# U_I.net
KiCad netlist of a schematic drawn in EAGLE
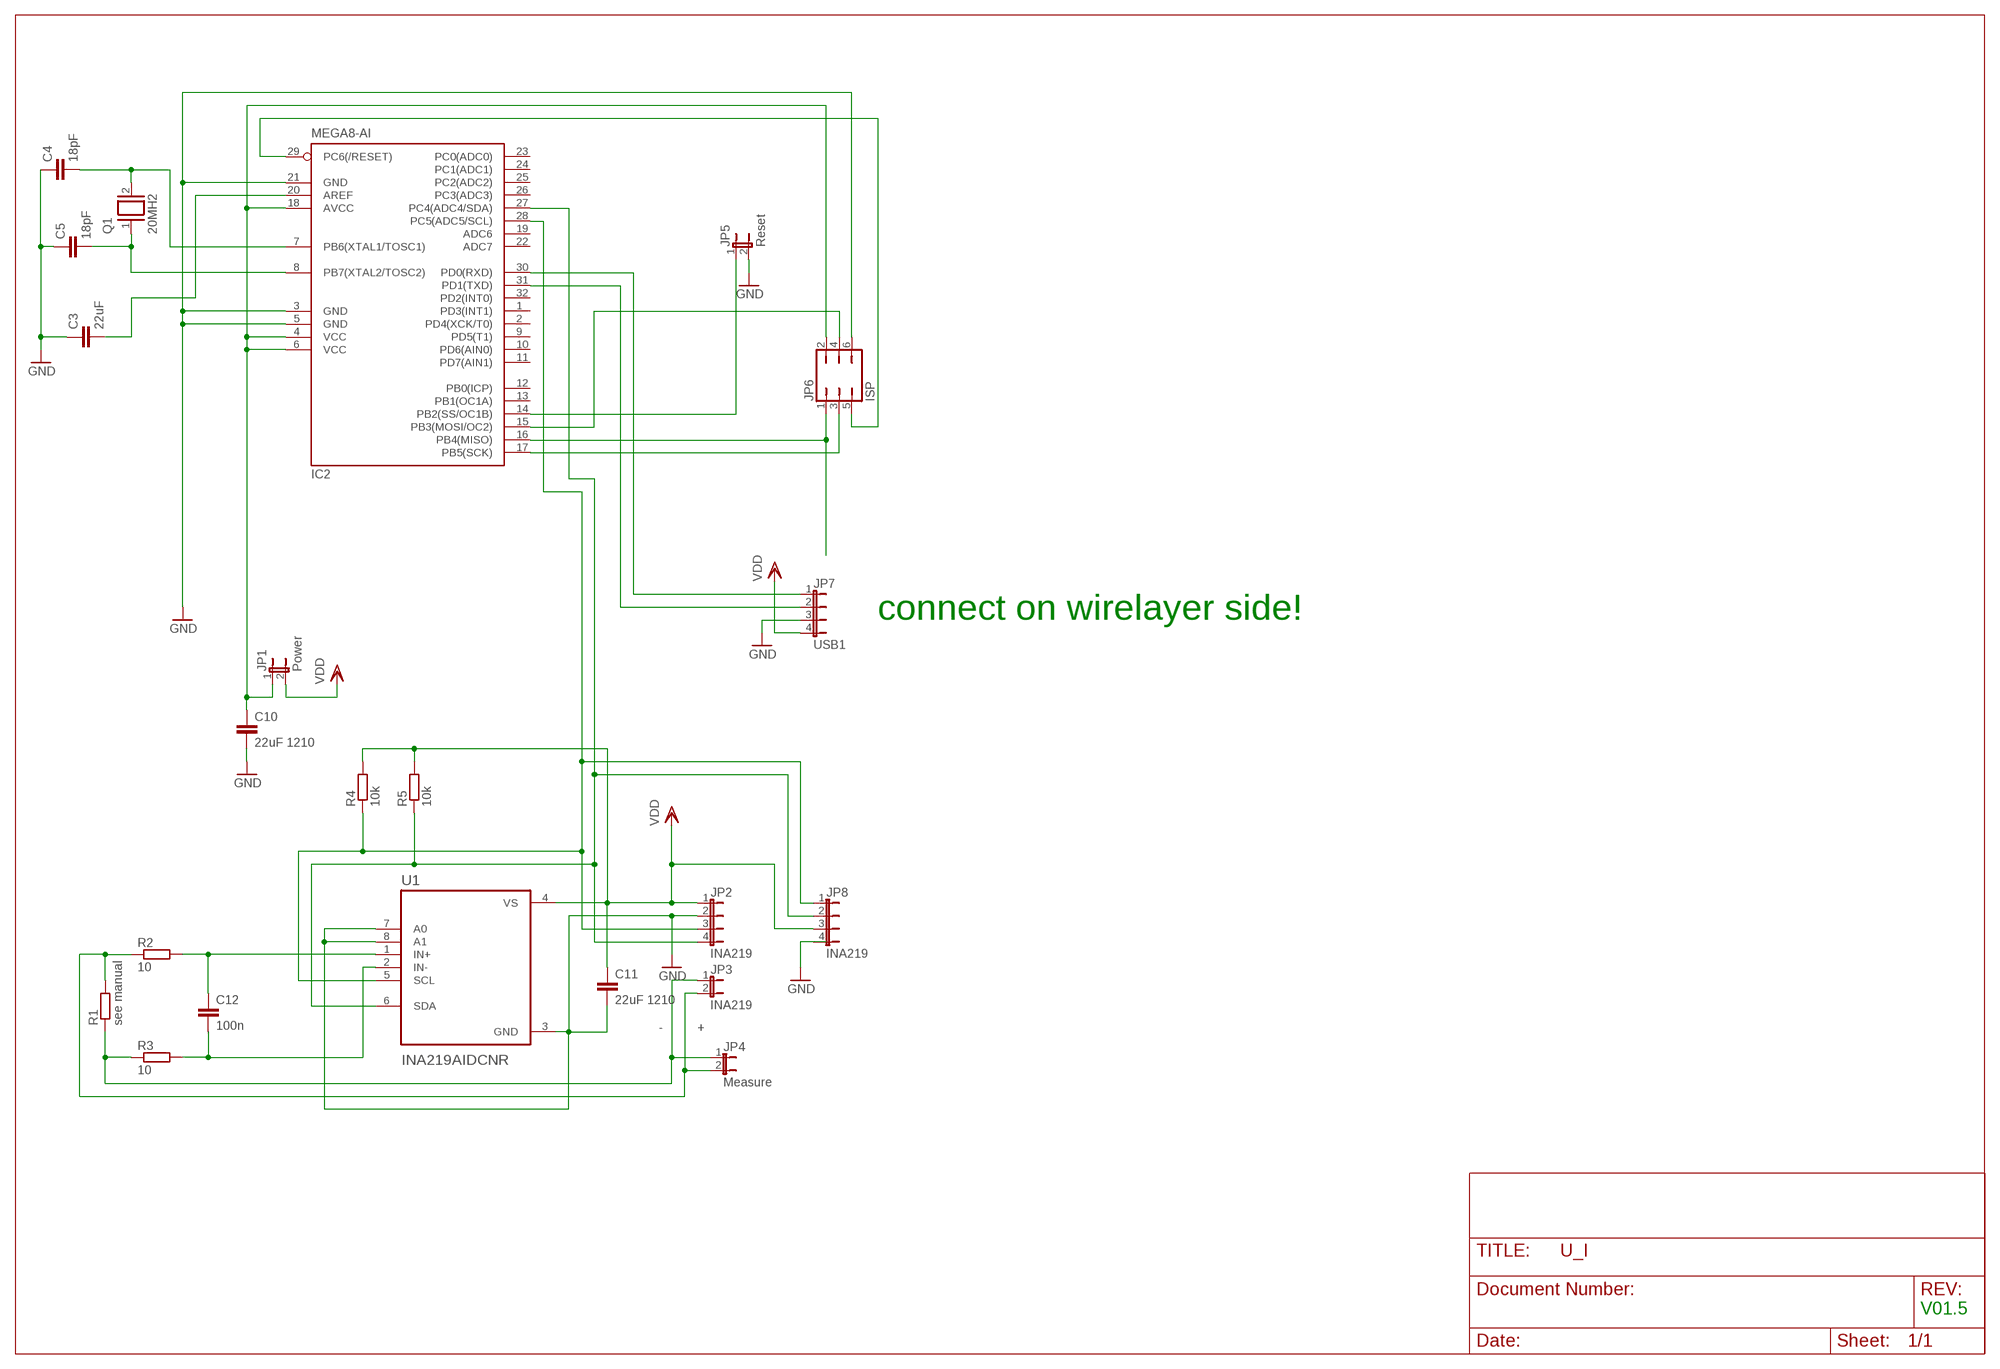
[diagram p0: schematic, sheet 1]

(export (version "E")
  (design (tool "Eeschema 10.0.6"))
  (components
    (comp (ref "C3")
      (value "22uF")
      (footprint "eagle-import:C1206")
      (libsource (lib "eagle-import") (part "C-EUC1206"))
    )
    (comp (ref "C4")
      (value "18pF")
      (footprint "eagle-import:C025-025X050")
      (libsource (lib "eagle-import") (part "resistor_C-EU025-025X050"))
    )
    (comp (ref "C5")
      (value "18pF")
      (footprint "eagle-import:C025-025X050")
      (libsource (lib "eagle-import") (part "resistor_C-EU025-025X050"))
    )
    (comp (ref "C10")
      (value "22uF 1210")
      (footprint "eagle-import:C1206")
      (libsource (lib "eagle-import") (part "C-EUC1206"))
    )
    (comp (ref "C11")
      (value "22uF 1210")
      (footprint "eagle-import:C1206")
      (libsource (lib "eagle-import") (part "C-EUC1206"))
    )
    (comp (ref "C12")
      (value "100n")
      (footprint "eagle-import:C1206")
      (libsource (lib "eagle-import") (part "C-EUC1206"))
    )
    (comp (ref "IC2")
      (value "MEGA8-AI")
      (footprint "eagle-import:TQFP32-08")
      (fields (field (name "MPN") "ATMEGA8-16AU"))
      (libsource (lib "eagle-import") (part "MEGA8-AI"))
    )
    (comp (ref "JP1")
      (value "Power")
      (footprint "eagle-import:JP1")
      (libsource (lib "eagle-import") (part "JP1E"))
    )
    (comp (ref "JP2")
      (value "INA219")
      (footprint "eagle-import:JP4")
      (libsource (lib "eagle-import") (part "JP4E"))
    )
    (comp (ref "JP3")
      (value "INA219")
      (footprint "eagle-import:JP1")
      (libsource (lib "eagle-import") (part "JP1E"))
    )
    (comp (ref "JP4")
      (value "Measure")
      (footprint "eagle-import:JP1")
      (libsource (lib "eagle-import") (part "JP1E"))
    )
    (comp (ref "JP5")
      (value "Reset")
      (footprint "eagle-import:JP1")
      (libsource (lib "eagle-import") (part "JP1E"))
    )
    (comp (ref "JP6")
      (value "ISP")
      (footprint "eagle-import:JP3Q")
      (libsource (lib "eagle-import") (part "JP3Q"))
    )
    (comp (ref "JP7")
      (value "USB1")
      (footprint "eagle-import:JP4")
      (libsource (lib "eagle-import") (part "JP4E"))
    )
    (comp (ref "JP8")
      (value "INA219")
      (footprint "eagle-import:JP4")
      (libsource (lib "eagle-import") (part "JP4E"))
    )
    (comp (ref "Q1")
      (value "20MH2")
      (footprint "eagle-import:QS")
      (libsource (lib "eagle-import") (part "XTAL/S"))
    )
    (comp (ref "R1")
      (value "see manual")
      (footprint "eagle-import:R1210")
      (libsource (lib "eagle-import") (part "R-EU_R1210"))
    )
    (comp (ref "R2")
      (value "10")
      (footprint "eagle-import:R1206")
      (libsource (lib "eagle-import") (part "R-EU_R1206"))
    )
    (comp (ref "R3")
      (value "10")
      (footprint "eagle-import:R1206")
      (libsource (lib "eagle-import") (part "R-EU_R1206"))
    )
    (comp (ref "R4")
      (value "10k")
      (footprint "eagle-import:R1206")
      (libsource (lib "eagle-import") (part "R-EU_R1206"))
    )
    (comp (ref "R5")
      (value "10k")
      (footprint "eagle-import:R1206")
      (libsource (lib "eagle-import") (part "R-EU_R1206"))
    )
    (comp (ref "U1")
      (value "INA219AIDCNR")
      (footprint "eagle-import:SOT65P280X145-8N")
      (fields (field (name "MF") "Texas Instruments"))
      (libsource (lib "eagle-import") (part "INA219AIDCNR"))
    )
  )
  (nets
    (net (code "1") (name "/+") (class "Default")
      (node (ref "JP3") (pin "2") (pinfunction "2_2") (pintype "passive"))
      (node (ref "JP4") (pin "2") (pinfunction "2_2") (pintype "passive"))
      (node (ref "R1") (pin "2") (pinfunction "2_2") (pintype "passive"))
      (node (ref "R2") (pin "1") (pinfunction "1_1") (pintype "passive"))
    )
    (net (code "2") (name "/-") (class "Default")
      (node (ref "JP3") (pin "1") (pinfunction "1_1") (pintype "passive"))
      (node (ref "JP4") (pin "1") (pinfunction "1_1") (pintype "passive"))
      (node (ref "R1") (pin "1") (pinfunction "1_1") (pintype "passive"))
      (node (ref "R3") (pin "1") (pinfunction "1_1") (pintype "passive"))
    )
    (net (code "3") (name "GND") (class "Default")
      (node (ref "C10") (pin "2") (pinfunction "2_2") (pintype "passive"))
      (node (ref "C11") (pin "2") (pinfunction "2_2") (pintype "passive"))
      (node (ref "C3") (pin "1") (pinfunction "1_1") (pintype "passive"))
      (node (ref "C4") (pin "1") (pinfunction "1_1") (pintype "passive"))
      (node (ref "C5") (pin "1") (pinfunction "1_1") (pintype "passive"))
      (node (ref "IC2") (pin "21") (pinfunction "GND_21") (pintype "power_in"))
      (node (ref "IC2") (pin "3") (pinfunction "GND_3") (pintype "power_in"))
      (node (ref "IC2") (pin "5") (pinfunction "GND_5") (pintype "power_in"))
      (node (ref "JP2") (pin "2") (pinfunction "2_2") (pintype "passive"))
      (node (ref "JP5") (pin "2") (pinfunction "2_2") (pintype "passive"))
      (node (ref "JP6") (pin "6") (pinfunction "6_6") (pintype "passive"))
      (node (ref "JP7") (pin "3") (pinfunction "3_3") (pintype "passive"))
      (node (ref "U1") (pin "3") (pinfunction "GND_3") (pintype "power_in"))
      (node (ref "U1") (pin "7") (pinfunction "A0_7") (pintype "input"))
      (node (ref "U1") (pin "8") (pinfunction "A1_8") (pintype "input"))
    )
    (net (code "4") (name "Net-(IC2-AREF)") (class "Default")
      (node (ref "C3") (pin "2") (pinfunction "2_2") (pintype "passive"))
      (node (ref "IC2") (pin "20") (pinfunction "AREF_20") (pintype "passive"))
    )
    (net (code "5") (name "Net-(IC2-AVCC)") (class "Default")
      (node (ref "C10") (pin "1") (pinfunction "1_1") (pintype "passive"))
      (node (ref "IC2") (pin "18") (pinfunction "AVCC_18") (pintype "power_in"))
      (node (ref "IC2") (pin "4") (pinfunction "VCC_4") (pintype "power_in"))
      (node (ref "IC2") (pin "6") (pinfunction "VCC_6") (pintype "power_in"))
      (node (ref "JP1") (pin "1") (pinfunction "1_1") (pintype "passive"))
      (node (ref "JP6") (pin "2") (pinfunction "2_2") (pintype "passive"))
    )
    (net (code "6") (name "Net-(IC2-PB2(SS{slash}OC1B))") (class "Default")
      (node (ref "IC2") (pin "14") (pinfunction "PB2(SS/OC1B)_14") (pintype "bidirectional"))
      (node (ref "JP5") (pin "1") (pinfunction "1_1") (pintype "passive"))
    )
    (net (code "7") (name "Net-(IC2-PB3(MOSI{slash}OC2))") (class "Default")
      (node (ref "IC2") (pin "15") (pinfunction "PB3(MOSI/OC2)_15") (pintype "bidirectional"))
      (node (ref "JP6") (pin "4") (pinfunction "4_4") (pintype "passive"))
    )
    (net (code "8") (name "Net-(IC2-PB4(MISO))") (class "Default")
      (node (ref "IC2") (pin "16") (pinfunction "PB4(MISO)_16") (pintype "bidirectional"))
      (node (ref "JP6") (pin "1") (pinfunction "1_1") (pintype "passive"))
    )
    (net (code "9") (name "Net-(IC2-PB5(SCK))") (class "Default")
      (node (ref "IC2") (pin "17") (pinfunction "PB5(SCK)_17") (pintype "bidirectional"))
      (node (ref "JP6") (pin "3") (pinfunction "3_3") (pintype "passive"))
    )
    (net (code "10") (name "Net-(IC2-PB6(XTAL1{slash}TOSC1))") (class "Default")
      (node (ref "C4") (pin "2") (pinfunction "2_2") (pintype "passive"))
      (node (ref "IC2") (pin "7") (pinfunction "PB6(XTAL1/TOSC1)_7") (pintype "bidirectional"))
      (node (ref "Q1") (pin "2") (pinfunction "2_2") (pintype "passive"))
    )
    (net (code "11") (name "Net-(IC2-PB7(XTAL2{slash}TOSC2))") (class "Default")
      (node (ref "C5") (pin "2") (pinfunction "2_2") (pintype "passive"))
      (node (ref "IC2") (pin "8") (pinfunction "PB7(XTAL2/TOSC2)_8") (pintype "bidirectional"))
      (node (ref "Q1") (pin "1") (pinfunction "1_1") (pintype "passive"))
    )
    (net (code "12") (name "Net-(IC2-PC4(ADC4{slash}SDA))") (class "Default")
      (node (ref "IC2") (pin "27") (pinfunction "PC4(ADC4/SDA)_27") (pintype "bidirectional"))
      (node (ref "JP2") (pin "4") (pinfunction "4_4") (pintype "passive"))
      (node (ref "JP8") (pin "2") (pinfunction "2_2") (pintype "passive"))
      (node (ref "R5") (pin "1") (pinfunction "1_1") (pintype "passive"))
      (node (ref "U1") (pin "6") (pinfunction "SDA_6") (pintype "bidirectional"))
    )
    (net (code "13") (name "Net-(IC2-PC5(ADC5{slash}SCL))") (class "Default")
      (node (ref "IC2") (pin "28") (pinfunction "PC5(ADC5/SCL)_28") (pintype "bidirectional"))
      (node (ref "JP2") (pin "3") (pinfunction "3_3") (pintype "passive"))
      (node (ref "JP8") (pin "1") (pinfunction "1_1") (pintype "passive"))
      (node (ref "R4") (pin "1") (pinfunction "1_1") (pintype "passive"))
      (node (ref "U1") (pin "5") (pinfunction "SCL_5") (pintype "input"))
    )
    (net (code "14") (name "Net-(IC2-PC6({slash}RESET))") (class "Default")
      (node (ref "IC2") (pin "29") (pinfunction "PC6(/RESET)_29") (pintype "bidirectional"))
      (node (ref "JP6") (pin "5") (pinfunction "5_5") (pintype "passive"))
    )
    (net (code "15") (name "Net-(IC2-PD0(RXD))") (class "Default")
      (node (ref "IC2") (pin "30") (pinfunction "PD0(RXD)_30") (pintype "bidirectional"))
      (node (ref "JP7") (pin "1") (pinfunction "1_1") (pintype "passive"))
    )
    (net (code "16") (name "Net-(IC2-PD1(TXD))") (class "Default")
      (node (ref "IC2") (pin "31") (pinfunction "PD1(TXD)_31") (pintype "bidirectional"))
      (node (ref "JP7") (pin "2") (pinfunction "2_2") (pintype "passive"))
    )
    (net (code "17") (name "Net-(U1-IN+)") (class "Default")
      (node (ref "C12") (pin "1") (pinfunction "1_1") (pintype "passive"))
      (node (ref "R2") (pin "2") (pinfunction "2_2") (pintype "passive"))
      (node (ref "U1") (pin "1") (pinfunction "IN+_1") (pintype "input"))
    )
    (net (code "18") (name "Net-(U1-IN-)") (class "Default")
      (node (ref "C12") (pin "2") (pinfunction "2_2") (pintype "passive"))
      (node (ref "R3") (pin "2") (pinfunction "2_2") (pintype "passive"))
      (node (ref "U1") (pin "2") (pinfunction "IN-_2") (pintype "input"))
    )
    (net (code "19") (name "VDD") (class "Default")
      (node (ref "C11") (pin "1") (pinfunction "1_1") (pintype "passive"))
      (node (ref "JP1") (pin "2") (pinfunction "2_2") (pintype "passive"))
      (node (ref "JP2") (pin "1") (pinfunction "1_1") (pintype "passive"))
      (node (ref "JP7") (pin "4") (pinfunction "4_4") (pintype "passive"))
      (node (ref "JP8") (pin "3") (pinfunction "3_3") (pintype "passive"))
      (node (ref "R4") (pin "2") (pinfunction "2_2") (pintype "passive"))
      (node (ref "R5") (pin "2") (pinfunction "2_2") (pintype "passive"))
      (node (ref "U1") (pin "4") (pinfunction "VS_4") (pintype "power_in"))
    )
    (net (code "20") (name "unconnected-(IC2-ADC6-Pad19)") (class "Default")
      (node (ref "IC2") (pin "19") (pinfunction "ADC6_19") (pintype "bidirectional"))
    )
    (net (code "21") (name "unconnected-(IC2-ADC7-Pad22)") (class "Default")
      (node (ref "IC2") (pin "22") (pinfunction "ADC7_22") (pintype "bidirectional"))
    )
    (net (code "22") (name "unconnected-(IC2-PB0(ICP)-Pad12)") (class "Default")
      (node (ref "IC2") (pin "12") (pinfunction "PB0(ICP)_12") (pintype "bidirectional"))
    )
    (net (code "23") (name "unconnected-(IC2-PB1(OC1A)-Pad13)") (class "Default")
      (node (ref "IC2") (pin "13") (pinfunction "PB1(OC1A)_13") (pintype "bidirectional"))
    )
    (net (code "24") (name "unconnected-(IC2-PC0(ADC0)-Pad23)") (class "Default")
      (node (ref "IC2") (pin "23") (pinfunction "PC0(ADC0)_23") (pintype "bidirectional"))
    )
    (net (code "25") (name "unconnected-(IC2-PC1(ADC1)-Pad24)") (class "Default")
      (node (ref "IC2") (pin "24") (pinfunction "PC1(ADC1)_24") (pintype "bidirectional"))
    )
    (net (code "26") (name "unconnected-(IC2-PC2(ADC2)-Pad25)") (class "Default")
      (node (ref "IC2") (pin "25") (pinfunction "PC2(ADC2)_25") (pintype "bidirectional"))
    )
    (net (code "27") (name "unconnected-(IC2-PC3(ADC3)-Pad26)") (class "Default")
      (node (ref "IC2") (pin "26") (pinfunction "PC3(ADC3)_26") (pintype "bidirectional"))
    )
    (net (code "28") (name "unconnected-(IC2-PD2(INT0)-Pad32)") (class "Default")
      (node (ref "IC2") (pin "32") (pinfunction "PD2(INT0)_32") (pintype "bidirectional"))
    )
    (net (code "29") (name "unconnected-(IC2-PD3(INT1)-Pad1)") (class "Default")
      (node (ref "IC2") (pin "1") (pinfunction "PD3(INT1)_1") (pintype "bidirectional"))
    )
    (net (code "30") (name "unconnected-(IC2-PD4(XCK{slash}T0)-Pad2)") (class "Default")
      (node (ref "IC2") (pin "2") (pinfunction "PD4(XCK/T0)_2") (pintype "bidirectional"))
    )
    (net (code "31") (name "unconnected-(IC2-PD5(T1)-Pad9)") (class "Default")
      (node (ref "IC2") (pin "9") (pinfunction "PD5(T1)_9") (pintype "bidirectional"))
    )
    (net (code "32") (name "unconnected-(IC2-PD6(AIN0)-Pad10)") (class "Default")
      (node (ref "IC2") (pin "10") (pinfunction "PD6(AIN0)_10") (pintype "bidirectional"))
    )
    (net (code "33") (name "unconnected-(IC2-PD7(AIN1)-Pad11)") (class "Default")
      (node (ref "IC2") (pin "11") (pinfunction "PD7(AIN1)_11") (pintype "bidirectional"))
    )
    (net (code "34") (name "unconnected-(JP8-Pad4)") (class "Default")
      (node (ref "JP8") (pin "4") (pinfunction "4_4") (pintype "passive"))
    )
  )
)
